# class_d_amp2.net
KiCad netlist of a schematic drawn in EasyEDA Pro
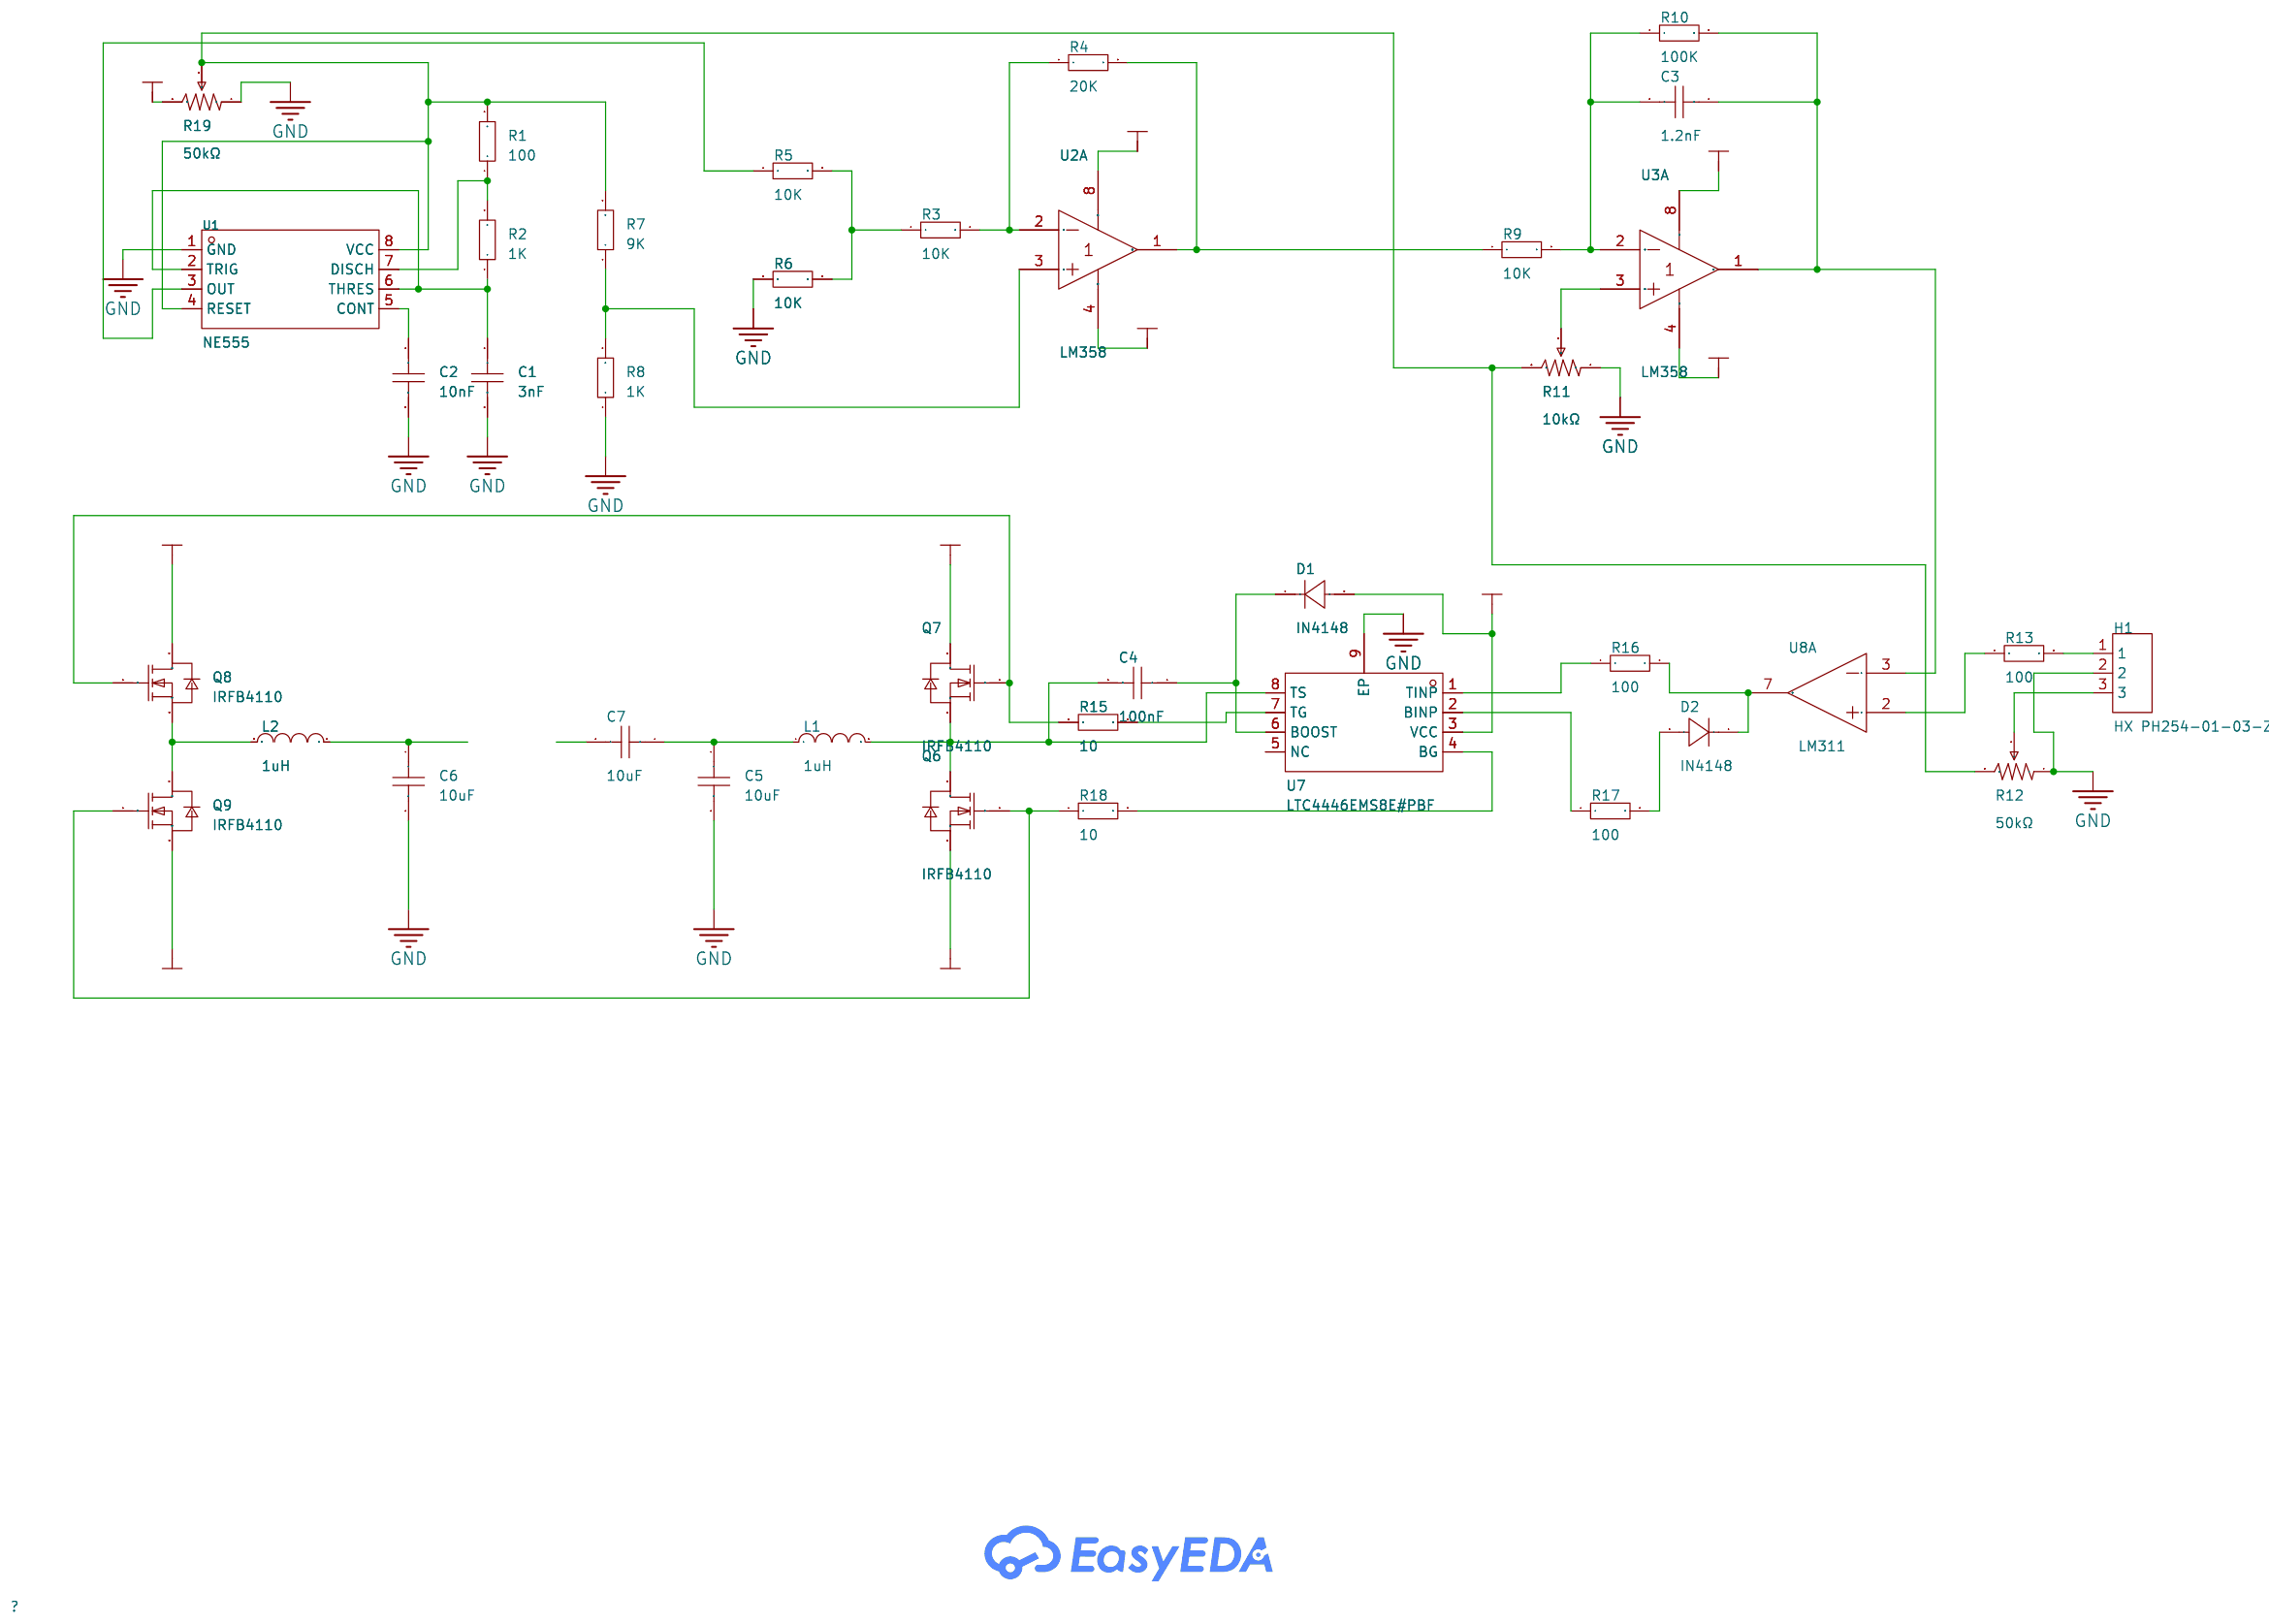
[diagram p0: schematic sheet]

(export (version "E")
  (design (tool "Eeschema 10.0.6"))
  (components
    (comp (ref "C1") (value "3nF") (footprint "easyedapro:C0603") (libsource (lib "easyedapro") (part "CAP")))
    (comp (ref "C2")
      (value "10nF")
      (footprint "easyedapro:C0603")
      (libsource (lib "easyedapro") (part "CAP"))
    )
    (comp (ref "C3")
      (value "1.2nF")
      (footprint "easyedapro:C0603")
      (libsource (lib "easyedapro") (part "CAP"))
    )
    (comp (ref "C4")
      (value "100nF")
      (footprint "easyedapro:C0603")
      (libsource (lib "easyedapro") (part "CAP"))
    )
    (comp (ref "C5")
      (value "10uF")
      (footprint "easyedapro:C0603")
      (libsource (lib "easyedapro") (part "CAP"))
    )
    (comp (ref "C6")
      (value "10uF")
      (footprint "easyedapro:C0603")
      (libsource (lib "easyedapro") (part "CAP"))
    )
    (comp (ref "C7")
      (value "10uF")
      (footprint "easyedapro:C0603")
      (libsource (lib "easyedapro") (part "CAP"))
    )
    (comp (ref "D1")
      (value "IN4148")
      (footprint "easyedapro:LL-34_L3.4-W1.5-RD")
      (libsource (lib "easyedapro") (part "IN4148_C9900023201"))
    )
    (comp (ref "D2")
      (value "IN4148")
      (footprint "easyedapro:LL-34_L3.4-W1.5-RD")
      (libsource (lib "easyedapro") (part "IN4148_C9900023201"))
    )
    (comp (ref "H1")
      (value "HX PH254-01-03-Z-L11.5 pcb pin header")
      (footprint "easyedapro:HDR-TH_3P-P2.54-V-M-1")
      (fields (field (name "Manufacturer") "hanxia(韩下)"))
      (libsource (lib "easyedapro") (part "HX PH254-01-03-Z-L11.5 PCB PIN HEADER"))
    )
    (comp (ref "L1") (value "1uH") (footprint "easyedapro:L0603") (libsource (lib "easyedapro") (part "电感")))
    (comp (ref "L2") (value "1uH") (footprint "easyedapro:L0603") (libsource (lib "easyedapro") (part "电感")))
    (comp (ref "Q6")
      (value "IRFB4110")
      (footprint "easyedapro:TO-220-3_L10.0-W4.6-P2.54-L")
      (fields (field (name "Manufacturer") "minos(迈诺斯)"))
      (libsource (lib "easyedapro") (part "IRFB4110"))
    )
    (comp (ref "Q7")
      (value "IRFB4110")
      (footprint "easyedapro:TO-220-3_L10.0-W4.6-P2.54-L")
      (fields (field (name "Manufacturer") "minos(迈诺斯)"))
      (libsource (lib "easyedapro") (part "IRFB4110"))
    )
    (comp (ref "Q8")
      (value "IRFB4110")
      (footprint "easyedapro:TO-220-3_L10.0-W4.6-P2.54-L")
      (fields (field (name "Manufacturer") "minos(迈诺斯)"))
      (libsource (lib "easyedapro") (part "IRFB4110"))
    )
    (comp (ref "Q9")
      (value "IRFB4110")
      (footprint "easyedapro:TO-220-3_L10.0-W4.6-P2.54-L")
      (fields (field (name "Manufacturer") "minos(迈诺斯)"))
      (libsource (lib "easyedapro") (part "IRFB4110"))
    )
    (comp (ref "R1") (value "100") (footprint "easyedapro:R0603") (libsource (lib "easyedapro") (part "Res")))
    (comp (ref "R2") (value "1K") (footprint "easyedapro:R0603") (libsource (lib "easyedapro") (part "Res")))
    (comp (ref "R3") (value "10K") (footprint "easyedapro:R0603") (libsource (lib "easyedapro") (part "Res")))
    (comp (ref "R4") (value "20K") (footprint "easyedapro:R0603") (libsource (lib "easyedapro") (part "Res")))
    (comp (ref "R5") (value "10K") (footprint "easyedapro:R0603") (libsource (lib "easyedapro") (part "Res")))
    (comp (ref "R6") (value "10K") (footprint "easyedapro:R0603") (libsource (lib "easyedapro") (part "Res")))
    (comp (ref "R7") (value "9K") (footprint "easyedapro:R0603") (libsource (lib "easyedapro") (part "Res")))
    (comp (ref "R8") (value "1K") (footprint "easyedapro:R0603") (libsource (lib "easyedapro") (part "Res")))
    (comp (ref "R9") (value "10K") (footprint "easyedapro:R0603") (libsource (lib "easyedapro") (part "Res")))
    (comp (ref "R10")
      (value "100K")
      (footprint "easyedapro:R0603")
      (libsource (lib "easyedapro") (part "Res"))
    )
    (comp (ref "R11")
      (value "10kΩ")
      (footprint "easyedapro:RES-ADJ-TH_3296W")
      (fields (field (name "Manufacturer Part") "3296W-503") (field (name "Manufacturer") "BAOTER(宝特)"))
      (libsource (lib "easyedapro") (part "3296W-503"))
    )
    (comp (ref "R12")
      (value "50kΩ")
      (footprint "easyedapro:RES-ADJ-TH_3296W")
      (fields (field (name "Manufacturer Part") "3296W-503") (field (name "Manufacturer") "BAOTER(宝特)"))
      (libsource (lib "easyedapro") (part "3296W-503"))
    )
    (comp (ref "R13")
      (value "100")
      (footprint "easyedapro:R0603")
      (libsource (lib "easyedapro") (part "Res"))
    )
    (comp (ref "R15") (value "10") (footprint "easyedapro:R0603") (libsource (lib "easyedapro") (part "Res")))
    (comp (ref "R16")
      (value "100")
      (footprint "easyedapro:R0603")
      (libsource (lib "easyedapro") (part "Res"))
    )
    (comp (ref "R17")
      (value "100")
      (footprint "easyedapro:R0603")
      (libsource (lib "easyedapro") (part "Res"))
    )
    (comp (ref "R18") (value "10") (footprint "easyedapro:R0603") (libsource (lib "easyedapro") (part "Res")))
    (comp (ref "R19")
      (value "50kΩ")
      (footprint "easyedapro:RES-ADJ-TH_3296W")
      (fields (field (name "Manufacturer Part") "3296W-503") (field (name "Manufacturer") "BAOTER(宝特)"))
      (libsource (lib "easyedapro") (part "3296W-503"))
    )
    (comp (ref "U1")
      (value "NE555")
      (footprint "easyedapro:SOIC-8_L4.9-W3.9-P1.27-LS6.0-BL")
      (fields (field (name "Manufacturer") "IDCHIP(英锐芯)"))
      (libsource (lib "easyedapro") (part "NE555_C5125085"))
    )
    (comp (ref "U2")
      (value "LM358")
      (footprint "easyedapro:SOP-8_L5.0-W3.9-P1.27-LS6.0-BL")
      (fields (field (name "Manufacturer") "KTP(科泰普)"))
      (libsource (lib "easyedapro") (part "LM358_C41379067"))
    )
    (comp (ref "U3")
      (value "LM358")
      (footprint "easyedapro:SOP-8_L5.0-W3.9-P1.27-LS6.0-BL")
      (fields (field (name "Manufacturer") "KTP(科泰普)"))
      (libsource (lib "easyedapro") (part "LM358_C41379067"))
    )
    (comp (ref "U7")
      (value "LTC4446EMS8E#PBF")
      (footprint "easyedapro:MSOP-8_L3.0-W3.0-P0.65-LS5.0-BL-EP")
      (fields (field (name "Manufacturer") "ADI(亚德诺)"))
      (libsource (lib "easyedapro") (part "LTC4446EMS8E#PBF"))
    )
    (comp (ref "U8")
      (value "LM311")
      (footprint "easyedapro:SOP-8_L4.9-W3.9-P1.27-LS6.0-BL")
      (fields (field (name "Manufacturer") "Gcore(扬州国芯)"))
      (libsource (lib "easyedapro") (part "LM311"))
    )
  )
  (nets
    (net (code "1") (name "+12V") (class "Default")
      (node (ref "D1") (pin "2") (pinfunction "A_2") (pintype "unspecified"))
      (node (ref "Q7") (pin "2") (pinfunction "D_2") (pintype "unspecified"))
      (node (ref "Q8") (pin "2") (pinfunction "D_2") (pintype "unspecified"))
      (node (ref "R19") (pin "3") (pinfunction "3_3") (pintype "unspecified"))
      (node (ref "U2") (pin "8") (pinfunction "VDD_8") (pintype "unspecified"))
      (node (ref "U3") (pin "8") (pinfunction "VDD_8") (pintype "unspecified"))
      (node (ref "U7") (pin "3") (pinfunction "VCC_3") (pintype "unspecified"))
    )
    (net (code "2") (name "-12V") (class "Default")
      (node (ref "Q6") (pin "3") (pinfunction "S_3") (pintype "unspecified"))
      (node (ref "Q9") (pin "3") (pinfunction "S_3") (pintype "unspecified"))
      (node (ref "U2") (pin "4") (pinfunction "VSS_4") (pintype "unspecified"))
      (node (ref "U3") (pin "4") (pinfunction "VSS_4") (pintype "unspecified"))
    )
    (net (code "3") (name "GND") (class "Default")
      (node (ref "C1") (pin "2") (pinfunction "2_2") (pintype "input"))
      (node (ref "C2") (pin "2") (pinfunction "2_2") (pintype "input"))
      (node (ref "C5") (pin "2") (pinfunction "2_2") (pintype "input"))
      (node (ref "C6") (pin "2") (pinfunction "2_2") (pintype "input"))
      (node (ref "H1") (pin "2") (pinfunction "2_2") (pintype "unspecified"))
      (node (ref "R11") (pin "1") (pinfunction "1_1") (pintype "unspecified"))
      (node (ref "R12") (pin "1") (pinfunction "1_1") (pintype "unspecified"))
      (node (ref "R19") (pin "1") (pinfunction "1_1") (pintype "unspecified"))
      (node (ref "R6") (pin "1") (pinfunction "1_1") (pintype "input"))
      (node (ref "R8") (pin "1") (pinfunction "1_1") (pintype "input"))
      (node (ref "U1") (pin "1") (pinfunction "GND_1") (pintype "input"))
      (node (ref "U7") (pin "9") (pinfunction "EP_9") (pintype "unspecified"))
    )
    (net (code "4") (name "Net-(C5-Pad1)") (class "Default")
      (node (ref "C5") (pin "1") (pinfunction "1_1") (pintype "input"))
      (node (ref "C7") (pin "1") (pinfunction "1_1") (pintype "input"))
      (node (ref "L1") (pin "1") (pinfunction "1_1") (pintype "input"))
    )
    (net (code "5") (name "Net-(C6-Pad1)") (class "Default")
      (node (ref "C6") (pin "1") (pinfunction "1_1") (pintype "input"))
      (node (ref "L2") (pin "1") (pinfunction "1_1") (pintype "input"))
    )
    (net (code "6") (name "Net-(D1-K)") (class "Default")
      (node (ref "C4") (pin "1") (pinfunction "1_1") (pintype "input"))
      (node (ref "D1") (pin "1") (pinfunction "K_1") (pintype "unspecified"))
      (node (ref "U7") (pin "6") (pinfunction "BOOST_6") (pintype "unspecified"))
    )
    (net (code "7") (name "Net-(D2-A)") (class "Default")
      (node (ref "D2") (pin "2") (pinfunction "A_2") (pintype "unspecified"))
      (node (ref "R17") (pin "2") (pinfunction "2_2") (pintype "input"))
    )
    (net (code "8") (name "Net-(D2-K)") (class "Default")
      (node (ref "D2") (pin "1") (pinfunction "K_1") (pintype "unspecified"))
      (node (ref "R16") (pin "2") (pinfunction "2_2") (pintype "input"))
      (node (ref "U8") (pin "7") (pinfunction "OUT_7") (pintype "output"))
    )
    (net (code "9") (name "Net-(H1-Pad1)") (class "Default")
      (node (ref "H1") (pin "1") (pinfunction "1_1") (pintype "unspecified"))
      (node (ref "R13") (pin "2") (pinfunction "2_2") (pintype "input"))
    )
    (net (code "10") (name "Net-(H1-Pad3)") (class "Default")
      (node (ref "H1") (pin "3") (pinfunction "3_3") (pintype "unspecified"))
      (node (ref "R12") (pin "2") (pinfunction "2_2") (pintype "unspecified"))
    )
    (net (code "11") (name "Net-(Q6-D)") (class "Default")
      (node (ref "C4") (pin "2") (pinfunction "2_2") (pintype "input"))
      (node (ref "L1") (pin "2") (pinfunction "2_2") (pintype "input"))
      (node (ref "Q6") (pin "2") (pinfunction "D_2") (pintype "unspecified"))
      (node (ref "Q7") (pin "3") (pinfunction "S_3") (pintype "unspecified"))
      (node (ref "U7") (pin "8") (pinfunction "TS_8") (pintype "unspecified"))
    )
    (net (code "12") (name "Net-(Q6-G)") (class "Default")
      (node (ref "Q6") (pin "1") (pinfunction "G_1") (pintype "unspecified"))
      (node (ref "Q9") (pin "1") (pinfunction "G_1") (pintype "unspecified"))
      (node (ref "R18") (pin "1") (pinfunction "1_1") (pintype "input"))
    )
    (net (code "13") (name "Net-(Q7-G)") (class "Default")
      (node (ref "Q7") (pin "1") (pinfunction "G_1") (pintype "unspecified"))
      (node (ref "Q8") (pin "1") (pinfunction "G_1") (pintype "unspecified"))
      (node (ref "R15") (pin "1") (pinfunction "1_1") (pintype "input"))
    )
    (net (code "14") (name "Net-(Q8-S)") (class "Default")
      (node (ref "L2") (pin "2") (pinfunction "2_2") (pintype "input"))
      (node (ref "Q8") (pin "3") (pinfunction "S_3") (pintype "unspecified"))
      (node (ref "Q9") (pin "2") (pinfunction "D_2") (pintype "unspecified"))
    )
    (net (code "15") (name "Net-(R3-Pad1)") (class "Default")
      (node (ref "R3") (pin "1") (pinfunction "1_1") (pintype "input"))
      (node (ref "R5") (pin "2") (pinfunction "2_2") (pintype "input"))
      (node (ref "R6") (pin "2") (pinfunction "2_2") (pintype "input"))
    )
    (net (code "16") (name "Net-(U1-CONT)") (class "Default")
      (node (ref "C2") (pin "1") (pinfunction "1_1") (pintype "input"))
      (node (ref "U1") (pin "5") (pinfunction "CONT_5") (pintype "input"))
    )
    (net (code "17") (name "Net-(U1-DISCH)") (class "Default")
      (node (ref "R1") (pin "1") (pinfunction "1_1") (pintype "input"))
      (node (ref "R2") (pin "2") (pinfunction "2_2") (pintype "input"))
      (node (ref "U1") (pin "7") (pinfunction "DISCH_7") (pintype "input"))
    )
    (net (code "18") (name "Net-(U1-OUT)") (class "Default")
      (node (ref "R5") (pin "1") (pinfunction "1_1") (pintype "input"))
      (node (ref "U1") (pin "3") (pinfunction "OUT_3") (pintype "input"))
    )
    (net (code "19") (name "Net-(U1-RESET)") (class "Default")
      (node (ref "R1") (pin "2") (pinfunction "2_2") (pintype "input"))
      (node (ref "R11") (pin "3") (pinfunction "3_3") (pintype "unspecified"))
      (node (ref "R12") (pin "3") (pinfunction "3_3") (pintype "unspecified"))
      (node (ref "R19") (pin "2") (pinfunction "2_2") (pintype "unspecified"))
      (node (ref "R7") (pin "2") (pinfunction "2_2") (pintype "input"))
      (node (ref "U1") (pin "4") (pinfunction "RESET_4") (pintype "input"))
      (node (ref "U1") (pin "8") (pinfunction "VCC_8") (pintype "input"))
    )
    (net (code "20") (name "Net-(U1-THRES)") (class "Default")
      (node (ref "C1") (pin "1") (pinfunction "1_1") (pintype "input"))
      (node (ref "R2") (pin "1") (pinfunction "1_1") (pintype "input"))
      (node (ref "U1") (pin "2") (pinfunction "TRIG_2") (pintype "input"))
      (node (ref "U1") (pin "6") (pinfunction "THRES_6") (pintype "input"))
    )
    (net (code "21") (name "Net-(U2A-+INA)") (class "Default")
      (node (ref "R7") (pin "1") (pinfunction "1_1") (pintype "input"))
      (node (ref "R8") (pin "2") (pinfunction "2_2") (pintype "input"))
      (node (ref "U2") (pin "3") (pinfunction "+INA_3") (pintype "unspecified"))
    )
    (net (code "22") (name "Net-(U2A--INA)") (class "Default")
      (node (ref "R3") (pin "2") (pinfunction "2_2") (pintype "input"))
      (node (ref "R4") (pin "1") (pinfunction "1_1") (pintype "input"))
      (node (ref "U2") (pin "2") (pinfunction "-INA_2") (pintype "unspecified"))
    )
    (net (code "23") (name "Net-(U2A-OUTA)") (class "Default")
      (node (ref "R4") (pin "2") (pinfunction "2_2") (pintype "input"))
      (node (ref "R9") (pin "1") (pinfunction "1_1") (pintype "input"))
      (node (ref "U2") (pin "1") (pinfunction "OUTA_1") (pintype "unspecified"))
    )
    (net (code "24") (name "Net-(U3A-+INA)") (class "Default")
      (node (ref "R11") (pin "2") (pinfunction "2_2") (pintype "unspecified"))
      (node (ref "U3") (pin "3") (pinfunction "+INA_3") (pintype "unspecified"))
    )
    (net (code "25") (name "Net-(U3A--INA)") (class "Default")
      (node (ref "C3") (pin "2") (pinfunction "2_2") (pintype "input"))
      (node (ref "R10") (pin "1") (pinfunction "1_1") (pintype "input"))
      (node (ref "R9") (pin "2") (pinfunction "2_2") (pintype "input"))
      (node (ref "U3") (pin "2") (pinfunction "-INA_2") (pintype "unspecified"))
    )
    (net (code "26") (name "Net-(U3A-OUTA)") (class "Default")
      (node (ref "C3") (pin "1") (pinfunction "1_1") (pintype "input"))
      (node (ref "R10") (pin "2") (pinfunction "2_2") (pintype "input"))
      (node (ref "U3") (pin "1") (pinfunction "OUTA_1") (pintype "unspecified"))
      (node (ref "U8") (pin "3") (pinfunction "IN-_3") (pintype "unspecified"))
    )
    (net (code "27") (name "Net-(U7-BG)") (class "Default")
      (node (ref "R18") (pin "2") (pinfunction "2_2") (pintype "input"))
      (node (ref "U7") (pin "4") (pinfunction "BG_4") (pintype "unspecified"))
    )
    (net (code "28") (name "Net-(U7-BINP)") (class "Default")
      (node (ref "R17") (pin "1") (pinfunction "1_1") (pintype "input"))
      (node (ref "U7") (pin "2") (pinfunction "BINP_2") (pintype "unspecified"))
    )
    (net (code "29") (name "Net-(U7-TG)") (class "Default")
      (node (ref "R15") (pin "2") (pinfunction "2_2") (pintype "input"))
      (node (ref "U7") (pin "7") (pinfunction "TG_7") (pintype "unspecified"))
    )
    (net (code "30") (name "Net-(U7-TINP)") (class "Default")
      (node (ref "R16") (pin "1") (pinfunction "1_1") (pintype "input"))
      (node (ref "U7") (pin "1") (pinfunction "TINP_1") (pintype "unspecified"))
    )
    (net (code "31") (name "Net-(U8A-IN+)") (class "Default")
      (node (ref "R13") (pin "1") (pinfunction "1_1") (pintype "input"))
      (node (ref "U8") (pin "2") (pinfunction "IN+_2") (pintype "unspecified"))
    )
    (net (code "32") (name "unconnected-(C7-Pad2)") (class "Default")
      (node (ref "C7") (pin "2") (pinfunction "2_2") (pintype "input"))
    )
    (net (code "33") (name "unconnected-(U7-NC-Pad5)") (class "Default")
      (node (ref "U7") (pin "5") (pinfunction "NC_5") (pintype "unspecified"))
    )
  )
)
